# 12Vto9V.net
KiCad netlist of a schematic drawn in Altium Designer
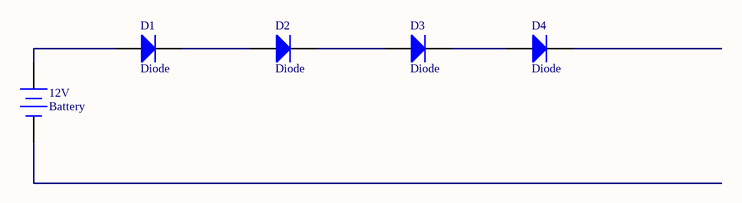
[diagram p0: 12Vto9V.SchDoc]

(export (version "E")
  (design (tool "Eeschema 10.0.6"))
  (components
    (comp (ref "12V")
      (value "Battery")
      (footprint "BAT-2")
      (description "Multicell Battery")
      (fields (field (name "PUBLISHER") "Altium Limited"))
      (libsource (lib "Miscellaneous Devices") (part "Battery"))
    )
    (comp (ref "D1")
      (value "Diode")
      (footprint "SMC")
      (description "Default Diode")
      (fields (field (name "PUBLISHER") "Altium Limited"))
      (libsource (lib "Miscellaneous Devices") (part "Diode"))
    )
    (comp (ref "D2")
      (value "Diode")
      (footprint "SMC")
      (description "Default Diode")
      (fields (field (name "PUBLISHER") "Altium Limited"))
      (libsource (lib "Miscellaneous Devices") (part "Diode"))
    )
    (comp (ref "D3")
      (value "Diode")
      (footprint "SMC")
      (description "Default Diode")
      (fields (field (name "PUBLISHER") "Altium Limited"))
      (libsource (lib "Miscellaneous Devices") (part "Diode"))
    )
    (comp (ref "D4")
      (value "Diode")
      (footprint "SMC")
      (description "Default Diode")
      (fields (field (name "PUBLISHER") "Altium Limited"))
      (libsource (lib "Miscellaneous Devices") (part "Diode"))
    )
  )
  (nets
    (net (code "1") (name "Net-(12V-+)") (class "Default")
      (node (ref "12V") (pin "1") (pinfunction "+_1") (pintype "passive"))
      (node (ref "D1") (pin "1") (pinfunction "A_1") (pintype "passive"))
    )
    (net (code "2") (name "Net-(D1-K)") (class "Default")
      (node (ref "D1") (pin "2") (pinfunction "K_2") (pintype "passive"))
      (node (ref "D2") (pin "1") (pinfunction "A_1") (pintype "passive"))
    )
    (net (code "3") (name "Net-(D2-K)") (class "Default")
      (node (ref "D2") (pin "2") (pinfunction "K_2") (pintype "passive"))
      (node (ref "D3") (pin "1") (pinfunction "A_1") (pintype "passive"))
    )
    (net (code "4") (name "Net-(D3-K)") (class "Default")
      (node (ref "D3") (pin "2") (pinfunction "K_2") (pintype "passive"))
      (node (ref "D4") (pin "1") (pinfunction "A_1") (pintype "passive"))
    )
    (net (code "5") (name "unconnected-(12V---Pad2)") (class "Default")
      (node (ref "12V") (pin "2") (pinfunction "-_2") (pintype "passive"))
    )
    (net (code "6") (name "unconnected-(D4-K-Pad2)") (class "Default")
      (node (ref "D4") (pin "2") (pinfunction "K_2") (pintype "passive"))
    )
  )
)
